# xbee_arriba.net
KiCad netlist of a schematic drawn in EAGLE
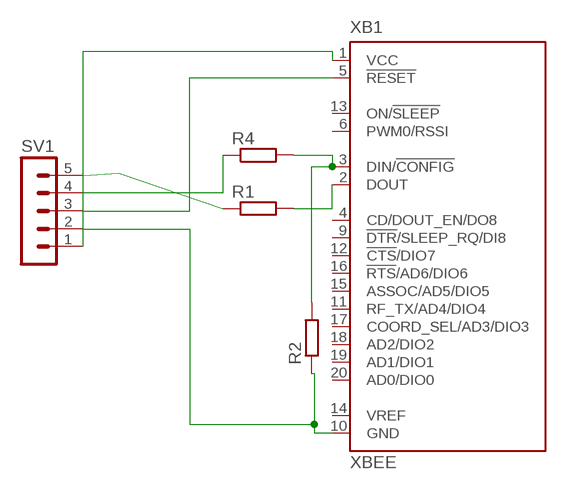
[diagram p0: schematic, sheet 1]

(export (version "E")
  (design (tool "Eeschema 10.0.6"))
  (components
    (comp (ref "R1")
      (value "R-EU_0204/7")
      (footprint "eagle-import:0204_7")
      (libsource (lib "eagle-import") (part "R-EU_0204/7"))
    )
    (comp (ref "R2")
      (value "R-EU_0204/7")
      (footprint "eagle-import:0204_7")
      (libsource (lib "eagle-import") (part "R-EU_0204/7"))
    )
    (comp (ref "R4")
      (value "R-EU_0204/7")
      (footprint "eagle-import:0204_7")
      (libsource (lib "eagle-import") (part "R-EU_0204/7"))
    )
    (comp (ref "SV1")
      (value "MA05-1")
      (footprint "eagle-import:MA05-1")
      (libsource (lib "eagle-import") (part "MA05-1"))
    )
    (comp (ref "XB1")
      (value "XBEE")
      (footprint "eagle-import:XBEE")
      (fields (field (name "MPN") "XBP24-Z7UIT-004"))
      (libsource (lib "eagle-import") (part "XBEE"))
    )
  )
  (nets
    (net (code "1") (name "Net-(R1-Pad1)") (class "Default")
      (node (ref "R1") (pin "1") (pinfunction "1_1") (pintype "passive"))
      (node (ref "SV1") (pin "5") (pinfunction "5_5") (pintype "passive"))
    )
    (net (code "2") (name "Net-(R4-Pad1)") (class "Default")
      (node (ref "R4") (pin "1") (pinfunction "1_1") (pintype "passive"))
      (node (ref "SV1") (pin "4") (pinfunction "4_4") (pintype "passive"))
    )
    (net (code "3") (name "Net-(XB1-DIN{slash}~{CONFIG})") (class "Default")
      (node (ref "R2") (pin "2") (pinfunction "2_2") (pintype "passive"))
      (node (ref "R4") (pin "2") (pinfunction "2_2") (pintype "passive"))
      (node (ref "XB1") (pin "3") (pinfunction "DIN/~{CONFIG}_3") (pintype "input"))
    )
    (net (code "4") (name "Net-(XB1-DOUT)") (class "Default")
      (node (ref "R1") (pin "2") (pinfunction "2_2") (pintype "passive"))
      (node (ref "XB1") (pin "2") (pinfunction "DOUT_2") (pintype "output"))
    )
    (net (code "5") (name "Net-(XB1-GND)") (class "Default")
      (node (ref "R2") (pin "1") (pinfunction "1_1") (pintype "passive"))
      (node (ref "SV1") (pin "2") (pinfunction "2_2") (pintype "passive"))
      (node (ref "XB1") (pin "10") (pinfunction "GND_10") (pintype "power_in"))
    )
    (net (code "6") (name "Net-(XB1-VCC)") (class "Default")
      (node (ref "SV1") (pin "1") (pinfunction "1_1") (pintype "passive"))
      (node (ref "XB1") (pin "1") (pinfunction "VCC_1") (pintype "power_in"))
    )
    (net (code "7") (name "Net-(XB1-~{RESET})") (class "Default")
      (node (ref "SV1") (pin "3") (pinfunction "3_3") (pintype "passive"))
      (node (ref "XB1") (pin "5") (pinfunction "~{RESET}_5") (pintype "input"))
    )
    (net (code "8") (name "unconnected-(XB1-AD0{slash}DIO0-Pad20)") (class "Default")
      (node (ref "XB1") (pin "20") (pinfunction "AD0/DIO0_20") (pintype "bidirectional"))
    )
    (net (code "9") (name "unconnected-(XB1-AD1{slash}DIO1-Pad19)") (class "Default")
      (node (ref "XB1") (pin "19") (pinfunction "AD1/DIO1_19") (pintype "bidirectional"))
    )
    (net (code "10") (name "unconnected-(XB1-AD2{slash}DIO2-Pad18)") (class "Default")
      (node (ref "XB1") (pin "18") (pinfunction "AD2/DIO2_18") (pintype "bidirectional"))
    )
    (net (code "11") (name "unconnected-(XB1-ASSOC{slash}AD5{slash}DIO5-Pad15)") (class "Default")
      (node (ref "XB1") (pin "15") (pinfunction "ASSOC/AD5/DIO5_15") (pintype "bidirectional"))
    )
    (net (code "12") (name "unconnected-(XB1-CD{slash}DOUT_EN{slash}DO8-Pad4)") (class "Default")
      (node (ref "XB1") (pin "4") (pinfunction "CD/DOUT_EN/DO8_4") (pintype "output"))
    )
    (net (code "13") (name "unconnected-(XB1-COORD_SEL{slash}AD3{slash}DIO3-Pad17)") (class "Default")
      (node (ref "XB1") (pin "17") (pinfunction "COORD_SEL/AD3/DIO3_17") (pintype "bidirectional"))
    )
    (net (code "14") (name "unconnected-(XB1-ON{slash}~{SLEEP}-Pad13)") (class "Default")
      (node (ref "XB1") (pin "13") (pinfunction "ON/~{SLEEP}_13") (pintype "output"))
    )
    (net (code "15") (name "unconnected-(XB1-PWM0{slash}RSSI-Pad6)") (class "Default")
      (node (ref "XB1") (pin "6") (pinfunction "PWM0/RSSI_6") (pintype "output"))
    )
    (net (code "16") (name "unconnected-(XB1-RF_TX{slash}AD4{slash}DIO4-Pad11)") (class "Default")
      (node (ref "XB1") (pin "11") (pinfunction "RF_TX/AD4/DIO4_11") (pintype "bidirectional"))
    )
    (net (code "17") (name "unconnected-(XB1-VREF-Pad14)") (class "Default")
      (node (ref "XB1") (pin "14") (pinfunction "VREF_14") (pintype "input"))
    )
    (net (code "18") (name "unconnected-(XB1-~{CTS}{slash}DIO7-Pad12)") (class "Default")
      (node (ref "XB1") (pin "12") (pinfunction "~{CTS}/DIO7_12") (pintype "bidirectional"))
    )
    (net (code "19") (name "unconnected-(XB1-~{DTR}{slash}SLEEP_RQ{slash}DI8-Pad9)") (class "Default")
      (node (ref "XB1") (pin "9") (pinfunction "~{DTR}/SLEEP_RQ/DI8_9") (pintype "bidirectional"))
    )
    (net (code "20") (name "unconnected-(XB1-~{RTS}{slash}AD6{slash}DIO6-Pad16)") (class "Default")
      (node (ref "XB1") (pin "16") (pinfunction "~{RTS}/AD6/DIO6_16") (pintype "bidirectional"))
    )
  )
)
